# badge.net
KiCad netlist of a schematic drawn in EAGLE
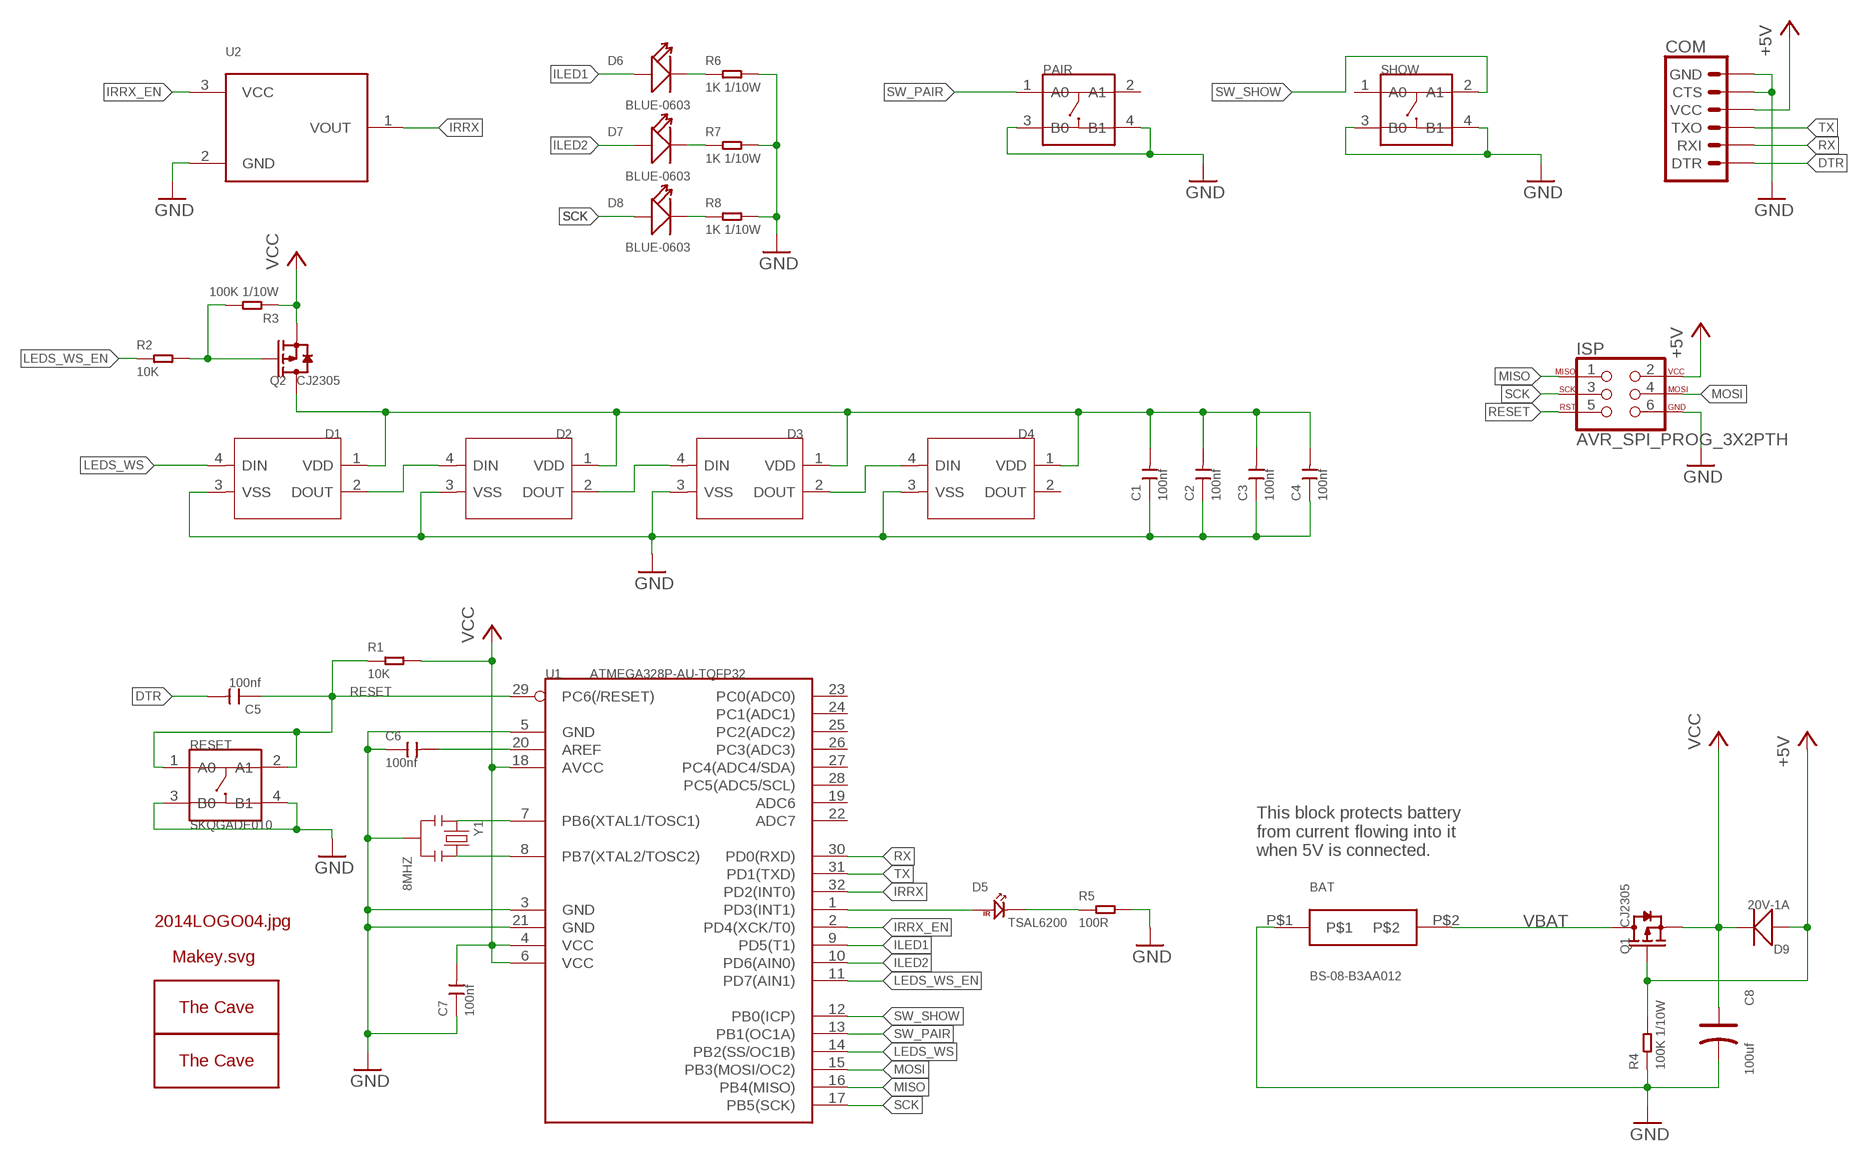
[diagram p0: schematic, sheet 1]

(export (version "E")
  (design (tool "Eeschema 10.0.6"))
  (components
    (comp (ref "BAT")
      (value "BS-08-B3AA012")
      (footprint "eagle-import:B3-08-B3AA012")
      (libsource (lib "eagle-import") (part "BS-08-B3AA012"))
    )
    (comp (ref "C1")
      (value "100nf")
      (footprint "eagle-import:C0603")
      (fields (field (name "MPN") "CC0603KRX7R9BB104"))
      (libsource (lib "eagle-import") (part "CERAMIC-100NF-50V-10%-X7R(0603)"))
    )
    (comp (ref "C2")
      (value "100nf")
      (footprint "eagle-import:C0603")
      (fields (field (name "MPN") "CC0603KRX7R9BB104"))
      (libsource (lib "eagle-import") (part "CERAMIC-100NF-50V-10%-X7R(0603)"))
    )
    (comp (ref "C3")
      (value "100nf")
      (footprint "eagle-import:C0603")
      (fields (field (name "MPN") "CC0603KRX7R9BB104"))
      (libsource (lib "eagle-import") (part "CERAMIC-100NF-50V-10%-X7R(0603)"))
    )
    (comp (ref "C4")
      (value "100nf")
      (footprint "eagle-import:C0603")
      (fields (field (name "MPN") "CC0603KRX7R9BB104"))
      (libsource (lib "eagle-import") (part "CERAMIC-100NF-50V-10%-X7R(0603)"))
    )
    (comp (ref "C5")
      (value "100nf")
      (footprint "eagle-import:C0603")
      (fields (field (name "MPN") "CC0603KRX7R9BB104"))
      (libsource (lib "eagle-import") (part "CERAMIC-100NF-50V-10%-X7R(0603)"))
    )
    (comp (ref "C6")
      (value "100nf")
      (footprint "eagle-import:C0603")
      (fields (field (name "MPN") "CC0603KRX7R9BB104"))
      (libsource (lib "eagle-import") (part "CERAMIC-100NF-50V-10%-X7R(0603)"))
    )
    (comp (ref "C7")
      (value "100nf")
      (footprint "eagle-import:C0603")
      (fields (field (name "MPN") "CC0603KRX7R9BB104"))
      (libsource (lib "eagle-import") (part "CERAMIC-100NF-50V-10%-X7R(0603)"))
    )
    (comp (ref "C8")
      (value "100uf")
      (footprint "eagle-import:AVX-B")
      (fields (field (name "MPN") "TAJB107M010#NJ"))
      (libsource (lib "eagle-import") (part "TANTALUM-SMD-100UF-10V(AVX-B)"))
    )
    (comp (ref "COM")
      (value "6_PIN_SERIAL_TARGETSILK")
      (footprint "eagle-import:6_PIN_SERIAL_TARGET_SIDE_W_SILK")
      (libsource (lib "eagle-import") (part "6_PIN_SERIAL_TARGETSILK"))
    )
    (comp (ref "D1")
      (value "SMD-RGB-LED-4P'WS2812B'")
      (footprint "eagle-import:LED4-SMD-5050")
      (libsource (lib "eagle-import") (part "SMD-RGB-LED-4P'WS2812B'"))
    )
    (comp (ref "D2")
      (value "SMD-RGB-LED-4P'WS2812B'")
      (footprint "eagle-import:LED4-SMD-5050")
      (libsource (lib "eagle-import") (part "SMD-RGB-LED-4P'WS2812B'"))
    )
    (comp (ref "D3")
      (value "SMD-RGB-LED-4P'WS2812B'")
      (footprint "eagle-import:LED4-SMD-5050")
      (libsource (lib "eagle-import") (part "SMD-RGB-LED-4P'WS2812B'"))
    )
    (comp (ref "D4")
      (value "SMD-RGB-LED-4P'WS2812B'")
      (footprint "eagle-import:LED4-SMD-5050")
      (libsource (lib "eagle-import") (part "SMD-RGB-LED-4P'WS2812B'"))
    )
    (comp (ref "D5")
      (value "TSAL6200")
      (footprint "eagle-import:TSAL6200")
      (libsource (lib "eagle-import") (part "TSAL6200"))
    )
    (comp (ref "D6")
      (value "BLUE-0603")
      (footprint "eagle-import:LED-0603")
      (fields (field (name "MPN") "19-217-BHC-ZL1M2RY-3T"))
      (libsource (lib "eagle-import") (part "SMD-LED-CLEAR-BLUE(0603)"))
    )
    (comp (ref "D7")
      (value "BLUE-0603")
      (footprint "eagle-import:LED-0603")
      (fields (field (name "MPN") "19-217-BHC-ZL1M2RY-3T"))
      (libsource (lib "eagle-import") (part "SMD-LED-CLEAR-BLUE(0603)"))
    )
    (comp (ref "D8")
      (value "BLUE-0603")
      (footprint "eagle-import:LED-0603")
      (fields (field (name "MPN") "19-217-BHC-ZL1M2RY-3T"))
      (libsource (lib "eagle-import") (part "SMD-LED-CLEAR-BLUE(0603)"))
    )
    (comp (ref "D9")
      (value "20V-1A")
      (footprint "eagle-import:SOD-123")
      (fields (field (name "MPN") "B5819W"))
      (libsource (lib "eagle-import") (part "SMD-DIODE-SCHOTTKY-20V-1A(SOD-123)"))
    )
    (comp (ref "ISP")
      (value "AVR_SPI_PROG_3X2PTH")
      (footprint "eagle-import:2X3")
      (libsource (lib "eagle-import") (part "AVR_SPI_PROG_3X2PTH"))
    )
    (comp (ref "PAIR")
      (value "SMD-BUTTON(4P-5.2X5.2X1.5MM-SKQGADE010)-SKQGADE010")
      (footprint "eagle-import:SW4-SMD-5.2X5.2X1.5MM")
      (fields (field (name "MPN") "SKQGADE010"))
      (libsource (lib "eagle-import") (part "SMD-BUTTON(4P-5.2X5.2X1.5MM-SKQGADE010)-SKQGADE010"))
    )
    (comp (ref "Q1")
      (value "CJ2305")
      (footprint "eagle-import:SOT-23")
      (libsource (lib "eagle-import") (part "SMD-MOSFET-P-CH-8V-4.1A-CJ2305(SOT-23)"))
    )
    (comp (ref "Q2")
      (value "CJ2305")
      (footprint "eagle-import:SOT-23")
      (libsource (lib "eagle-import") (part "SMD-MOSFET-P-CH-8V-4.1A-CJ2305(SOT-23)"))
    )
    (comp (ref "R1")
      (value "10K")
      (footprint "eagle-import:R0603")
      (fields (field (name "MPN") "RC0603FR-0710KL"))
      (libsource (lib "eagle-import") (part "SMD-RES-10K-1%-1/10W(0603)"))
    )
    (comp (ref "R2")
      (value "10K")
      (footprint "eagle-import:R0603")
      (fields (field (name "MPN") "RC0603FR-0710KL"))
      (libsource (lib "eagle-import") (part "SMD-RES-10K-1%-1/10W(0603)"))
    )
    (comp (ref "R3")
      (value "100K 1/10W")
      (footprint "eagle-import:R0603")
      (fields (field (name "MPN") "RC0603JR-07100KL"))
      (libsource (lib "eagle-import") (part "SMD-RES-100K-5%-1/10W(0603)"))
    )
    (comp (ref "R4")
      (value "100K 1/10W")
      (footprint "eagle-import:R0603")
      (fields (field (name "MPN") "RC0603JR-07100KL"))
      (libsource (lib "eagle-import") (part "SMD-RES-100K-5%-1/10W(0603)"))
    )
    (comp (ref "R5")
      (value "100R")
      (footprint "eagle-import:R0805")
      (fields (field (name "MPN") "RC0805JR-07100RL"))
      (libsource (lib "eagle-import") (part "SMD-RES-100R-5%-1/8W(0805)"))
    )
    (comp (ref "R6")
      (value "1K 1/10W")
      (footprint "eagle-import:R0603")
      (fields (field (name "MPN") "RC0603JR-071KL"))
      (libsource (lib "eagle-import") (part "SMD-RES-1K-5%-1/10W(0603)"))
    )
    (comp (ref "R7")
      (value "1K 1/10W")
      (footprint "eagle-import:R0603")
      (fields (field (name "MPN") "RC0603JR-071KL"))
      (libsource (lib "eagle-import") (part "SMD-RES-1K-5%-1/10W(0603)"))
    )
    (comp (ref "R8")
      (value "1K 1/10W")
      (footprint "eagle-import:R0603")
      (fields (field (name "MPN") "RC0603JR-071KL"))
      (libsource (lib "eagle-import") (part "SMD-RES-1K-5%-1/10W(0603)"))
    )
    (comp (ref "RESET")
      (value "SKQGADE010")
      (footprint "eagle-import:SW4-SMD-5.2X5.2X1.5MM")
      (libsource (lib "eagle-import") (part "SMD-BUTTON(4P-5.2X5.2X1.5MM-SKQGADE010)-SKQGADE010"))
    )
    (comp (ref "SHOW")
      (value "SMD-BUTTON(4P-5.2X5.2X1.5MM-SKQGADE010)-SKQGADE010")
      (footprint "eagle-import:SW4-SMD-5.2X5.2X1.5MM")
      (fields (field (name "MPN") "SKQGADE010"))
      (libsource (lib "eagle-import") (part "SMD-BUTTON(4P-5.2X5.2X1.5MM-SKQGADE010)-SKQGADE010"))
    )
    (comp (ref "U$1")
      (value "2014LOGO04#JPG")
      (footprint "eagle-import:2014LOGO04#JPG")
      (libsource (lib "eagle-import") (part "2014LOGO04#JPG"))
    )
    (comp (ref "U$2")
      (value "MAKEY#SVG")
      (footprint "eagle-import:MAKEY#SVG")
      (libsource (lib "eagle-import") (part "MAKEY#SVG"))
    )
    (comp (ref "U$3")
      (value "THECAVE_LOGO_NEW_TOP_SMALL")
      (footprint "eagle-import:NEW_LOGO_SMALL_TOP")
      (libsource (lib "eagle-import") (part "THECAVE_LOGO_NEW_TOP_SMALL"))
    )
    (comp (ref "U$4")
      (value "THECAVE_LOGO_NEW_COPPER_SMALL")
      (footprint "eagle-import:NEW_LOGO_SMALL_COPPER")
      (libsource (lib "eagle-import") (part "THECAVE_LOGO_NEW_COPPER_SMALL"))
    )
    (comp (ref "U1")
      (value "ATMEGA328P-AU-TQFP32")
      (footprint "eagle-import:TQFP32-0.8-7X7MM")
      (fields (field (name "MPN") "ATMEGA328P-AU"))
      (libsource (lib "eagle-import") (part "MCU-ATMEGA328P-AU(TQFP32)"))
    )
    (comp (ref "U2")
      (value "TSOP382")
      (footprint "eagle-import:TSOP382")
      (libsource (lib "eagle-import") (part "TSOP382"))
    )
    (comp (ref "Y1")
      (value "8MHZ")
      (footprint "eagle-import:X3-SMD-3.6X1.3X0.8MM")
      (libsource (lib "eagle-import") (part "SMD-CRYSTAL-8MHZ--0.3%-150R(3P-3.6X1.3MM)"))
    )
  )
  (nets
    (net (code "1") (name "+5V") (class "Default")
      (node (ref "COM") (pin "P$4") (pinfunction "VCC_P$4") (pintype "passive"))
      (node (ref "D9") (pin "+") (pinfunction "+_+") (pintype "passive"))
      (node (ref "ISP") (pin "2") (pinfunction "2_2") (pintype "passive"))
      (node (ref "Q1") (pin "1") (pinfunction "G_1") (pintype "passive"))
      (node (ref "R4") (pin "2") (pinfunction "2_2") (pintype "passive"))
    )
    (net (code "2") (name "/VBAT") (class "Default")
      (node (ref "BAT") (pin "P$2") (pinfunction "P$2_P$2") (pintype "bidirectional"))
      (node (ref "Q1") (pin "3") (pinfunction "D_3") (pintype "passive"))
    )
    (net (code "3") (name "DTR") (class "Default")
      (node (ref "C5") (pin "2") (pinfunction "2_2") (pintype "passive"))
      (node (ref "COM") (pin "P$1") (pinfunction "DTR_P$1") (pintype "passive"))
    )
    (net (code "4") (name "GND") (class "Default")
      (node (ref "BAT") (pin "P$1") (pinfunction "P$1_P$1") (pintype "bidirectional"))
      (node (ref "C1") (pin "1") (pinfunction "1_1") (pintype "passive"))
      (node (ref "C2") (pin "1") (pinfunction "1_1") (pintype "passive"))
      (node (ref "C3") (pin "1") (pinfunction "1_1") (pintype "passive"))
      (node (ref "C4") (pin "1") (pinfunction "1_1") (pintype "passive"))
      (node (ref "C6") (pin "1") (pinfunction "1_1") (pintype "passive"))
      (node (ref "C7") (pin "1") (pinfunction "1_1") (pintype "passive"))
      (node (ref "C8") (pin "-") (pinfunction "-_-") (pintype "passive"))
      (node (ref "COM") (pin "P$5") (pinfunction "CTS_P$5") (pintype "passive"))
      (node (ref "COM") (pin "P$6") (pinfunction "GND_P$6") (pintype "passive"))
      (node (ref "D1") (pin "3") (pinfunction "VSS_3") (pintype "bidirectional"))
      (node (ref "D2") (pin "3") (pinfunction "VSS_3") (pintype "bidirectional"))
      (node (ref "D3") (pin "3") (pinfunction "VSS_3") (pintype "bidirectional"))
      (node (ref "D4") (pin "3") (pinfunction "VSS_3") (pintype "bidirectional"))
      (node (ref "ISP") (pin "6") (pinfunction "6_6") (pintype "passive"))
      (node (ref "PAIR") (pin "3") (pinfunction "B0_3") (pintype "bidirectional"))
      (node (ref "PAIR") (pin "4") (pinfunction "B1_4") (pintype "bidirectional"))
      (node (ref "R4") (pin "1") (pinfunction "1_1") (pintype "passive"))
      (node (ref "R5") (pin "2") (pinfunction "2_2") (pintype "passive"))
      (node (ref "R6") (pin "2") (pinfunction "2_2") (pintype "passive"))
      (node (ref "R7") (pin "2") (pinfunction "2_2") (pintype "passive"))
      (node (ref "R8") (pin "2") (pinfunction "2_2") (pintype "passive"))
      (node (ref "RESET") (pin "3") (pinfunction "B0_3") (pintype "bidirectional"))
      (node (ref "RESET") (pin "4") (pinfunction "B1_4") (pintype "bidirectional"))
      (node (ref "SHOW") (pin "3") (pinfunction "B0_3") (pintype "bidirectional"))
      (node (ref "SHOW") (pin "4") (pinfunction "B1_4") (pintype "bidirectional"))
      (node (ref "U1") (pin "21") (pinfunction "GND_21") (pintype "bidirectional"))
      (node (ref "U1") (pin "3") (pinfunction "GND_3") (pintype "bidirectional"))
      (node (ref "U1") (pin "5") (pinfunction "GND_5") (pintype "bidirectional"))
      (node (ref "U2") (pin "2") (pinfunction "GND_2") (pintype "bidirectional"))
      (node (ref "Y1") (pin "2") (pinfunction "2_2") (pintype "passive"))
    )
    (net (code "5") (name "ILED1") (class "Default")
      (node (ref "D6") (pin "+") (pinfunction "+_+") (pintype "passive"))
      (node (ref "U1") (pin "9") (pinfunction "PD5(T1)_9") (pintype "bidirectional"))
    )
    (net (code "6") (name "ILED2") (class "Default")
      (node (ref "D7") (pin "+") (pinfunction "+_+") (pintype "passive"))
      (node (ref "U1") (pin "10") (pinfunction "PD6(AIN0)_10") (pintype "bidirectional"))
    )
    (net (code "7") (name "IRRX") (class "Default")
      (node (ref "U1") (pin "32") (pinfunction "PD2(INT0)_32") (pintype "bidirectional"))
      (node (ref "U2") (pin "1") (pinfunction "VOUT_1") (pintype "bidirectional"))
    )
    (net (code "8") (name "IRRX_EN") (class "Default")
      (node (ref "U1") (pin "2") (pinfunction "PD4(XCK/T0)_2") (pintype "bidirectional"))
      (node (ref "U2") (pin "3") (pinfunction "VCC_3") (pintype "bidirectional"))
    )
    (net (code "9") (name "LEDS_WS") (class "Default")
      (node (ref "D1") (pin "4") (pinfunction "DIN_4") (pintype "bidirectional"))
      (node (ref "U1") (pin "14") (pinfunction "PB2(SS/OC1B)_14") (pintype "bidirectional"))
    )
    (net (code "10") (name "LEDS_WS_EN") (class "Default")
      (node (ref "R2") (pin "1") (pinfunction "1_1") (pintype "passive"))
      (node (ref "U1") (pin "11") (pinfunction "PD7(AIN1)_11") (pintype "bidirectional"))
    )
    (net (code "11") (name "MISO") (class "Default")
      (node (ref "ISP") (pin "1") (pinfunction "1_1") (pintype "passive"))
      (node (ref "U1") (pin "16") (pinfunction "PB4(MISO)_16") (pintype "bidirectional"))
    )
    (net (code "12") (name "MOSI") (class "Default")
      (node (ref "ISP") (pin "4") (pinfunction "4_4") (pintype "passive"))
      (node (ref "U1") (pin "15") (pinfunction "PB3(MOSI/OC2)_15") (pintype "bidirectional"))
    )
    (net (code "13") (name "Net-(D1-DOUT)") (class "Default")
      (node (ref "D1") (pin "2") (pinfunction "DOUT_2") (pintype "bidirectional"))
      (node (ref "D2") (pin "4") (pinfunction "DIN_4") (pintype "bidirectional"))
    )
    (net (code "14") (name "Net-(D1-VDD)") (class "Default")
      (node (ref "C1") (pin "2") (pinfunction "2_2") (pintype "passive"))
      (node (ref "C2") (pin "2") (pinfunction "2_2") (pintype "passive"))
      (node (ref "C3") (pin "2") (pinfunction "2_2") (pintype "passive"))
      (node (ref "C4") (pin "2") (pinfunction "2_2") (pintype "passive"))
      (node (ref "D1") (pin "1") (pinfunction "VDD_1") (pintype "bidirectional"))
      (node (ref "D2") (pin "1") (pinfunction "VDD_1") (pintype "bidirectional"))
      (node (ref "D3") (pin "1") (pinfunction "VDD_1") (pintype "bidirectional"))
      (node (ref "D4") (pin "1") (pinfunction "VDD_1") (pintype "bidirectional"))
      (node (ref "Q2") (pin "3") (pinfunction "D_3") (pintype "passive"))
    )
    (net (code "15") (name "Net-(D2-DOUT)") (class "Default")
      (node (ref "D2") (pin "2") (pinfunction "DOUT_2") (pintype "bidirectional"))
      (node (ref "D3") (pin "4") (pinfunction "DIN_4") (pintype "bidirectional"))
    )
    (net (code "16") (name "Net-(D3-DOUT)") (class "Default")
      (node (ref "D3") (pin "2") (pinfunction "DOUT_2") (pintype "bidirectional"))
      (node (ref "D4") (pin "4") (pinfunction "DIN_4") (pintype "bidirectional"))
    )
    (net (code "17") (name "Net-(D5-PadN)") (class "Default")
      (node (ref "D5") (pin "N") (pinfunction "N_N") (pintype "bidirectional"))
      (node (ref "R5") (pin "1") (pinfunction "1_1") (pintype "passive"))
    )
    (net (code "18") (name "Net-(D6-Pad-)") (class "Default")
      (node (ref "D6") (pin "-") (pinfunction "-_-") (pintype "passive"))
      (node (ref "R6") (pin "1") (pinfunction "1_1") (pintype "passive"))
    )
    (net (code "19") (name "Net-(D7-Pad-)") (class "Default")
      (node (ref "D7") (pin "-") (pinfunction "-_-") (pintype "passive"))
      (node (ref "R7") (pin "1") (pinfunction "1_1") (pintype "passive"))
    )
    (net (code "20") (name "Net-(D8-Pad-)") (class "Default")
      (node (ref "D8") (pin "-") (pinfunction "-_-") (pintype "passive"))
      (node (ref "R8") (pin "1") (pinfunction "1_1") (pintype "passive"))
    )
    (net (code "21") (name "Net-(Q2-G)") (class "Default")
      (node (ref "Q2") (pin "1") (pinfunction "G_1") (pintype "passive"))
      (node (ref "R2") (pin "2") (pinfunction "2_2") (pintype "passive"))
      (node (ref "R3") (pin "2") (pinfunction "2_2") (pintype "passive"))
    )
    (net (code "22") (name "Net-(U1-AREF)") (class "Default")
      (node (ref "C6") (pin "2") (pinfunction "2_2") (pintype "passive"))
      (node (ref "U1") (pin "20") (pinfunction "AREF_20") (pintype "bidirectional"))
    )
    (net (code "23") (name "Net-(U1-PB6(XTAL1{slash}TOSC1))") (class "Default")
      (node (ref "U1") (pin "7") (pinfunction "PB6(XTAL1/TOSC1)_7") (pintype "bidirectional"))
      (node (ref "Y1") (pin "1") (pinfunction "1_1") (pintype "passive"))
    )
    (net (code "24") (name "Net-(U1-PB7(XTAL2{slash}TOSC2))") (class "Default")
      (node (ref "U1") (pin "8") (pinfunction "PB7(XTAL2/TOSC2)_8") (pintype "bidirectional"))
      (node (ref "Y1") (pin "3") (pinfunction "3_3") (pintype "passive"))
    )
    (net (code "25") (name "Net-(U1-PD3(INT1))") (class "Default")
      (node (ref "D5") (pin "P") (pinfunction "P_P") (pintype "bidirectional"))
      (node (ref "U1") (pin "1") (pinfunction "PD3(INT1)_1") (pintype "bidirectional"))
    )
    (net (code "26") (name "RESET") (class "Default")
      (node (ref "C5") (pin "1") (pinfunction "1_1") (pintype "passive"))
      (node (ref "ISP") (pin "5") (pinfunction "5_5") (pintype "passive"))
      (node (ref "R1") (pin "1") (pinfunction "1_1") (pintype "passive"))
      (node (ref "RESET") (pin "1") (pinfunction "A0_1") (pintype "bidirectional"))
      (node (ref "RESET") (pin "2") (pinfunction "A1_2") (pintype "bidirectional"))
      (node (ref "U1") (pin "29") (pinfunction "PC6(/RESET)_29") (pintype "bidirectional"))
    )
    (net (code "27") (name "RX") (class "Default")
      (node (ref "COM") (pin "P$3") (pinfunction "RXI_P$3") (pintype "passive"))
      (node (ref "U1") (pin "30") (pinfunction "PD0(RXD)_30") (pintype "bidirectional"))
    )
    (net (code "28") (name "SCK") (class "Default")
      (node (ref "D8") (pin "+") (pinfunction "+_+") (pintype "passive"))
      (node (ref "ISP") (pin "3") (pinfunction "3_3") (pintype "passive"))
      (node (ref "U1") (pin "17") (pinfunction "PB5(SCK)_17") (pintype "bidirectional"))
    )
    (net (code "29") (name "SW_PAIR") (class "Default")
      (node (ref "PAIR") (pin "1") (pinfunction "A0_1") (pintype "bidirectional"))
      (node (ref "U1") (pin "13") (pinfunction "PB1(OC1A)_13") (pintype "bidirectional"))
    )
    (net (code "30") (name "SW_SHOW") (class "Default")
      (node (ref "SHOW") (pin "2") (pinfunction "A1_2") (pintype "bidirectional"))
      (node (ref "U1") (pin "12") (pinfunction "PB0(ICP)_12") (pintype "bidirectional"))
    )
    (net (code "31") (name "TX") (class "Default")
      (node (ref "COM") (pin "P$2") (pinfunction "TXO_P$2") (pintype "passive"))
      (node (ref "U1") (pin "31") (pinfunction "PD1(TXD)_31") (pintype "bidirectional"))
    )
    (net (code "32") (name "VCC") (class "Default")
      (node (ref "C7") (pin "2") (pinfunction "2_2") (pintype "passive"))
      (node (ref "C8") (pin "+") (pinfunction "+_+") (pintype "passive"))
      (node (ref "D9") (pin "-") (pinfunction "-_-") (pintype "passive"))
      (node (ref "Q1") (pin "2") (pinfunction "S_2") (pintype "passive"))
      (node (ref "Q2") (pin "2") (pinfunction "S_2") (pintype "passive"))
      (node (ref "R1") (pin "2") (pinfunction "2_2") (pintype "passive"))
      (node (ref "R3") (pin "1") (pinfunction "1_1") (pintype "passive"))
      (node (ref "U1") (pin "18") (pinfunction "AVCC_18") (pintype "bidirectional"))
      (node (ref "U1") (pin "4") (pinfunction "VCC_4") (pintype "bidirectional"))
      (node (ref "U1") (pin "6") (pinfunction "VCC_6") (pintype "bidirectional"))
    )
    (net (code "33") (name "unconnected-(D4-DOUT-Pad2)") (class "Default")
      (node (ref "D4") (pin "2") (pinfunction "DOUT_2") (pintype "bidirectional"))
    )
    (net (code "34") (name "unconnected-(PAIR-A1-Pad2)") (class "Default")
      (node (ref "PAIR") (pin "2") (pinfunction "A1_2") (pintype "bidirectional"))
    )
    (net (code "35") (name "unconnected-(SHOW-A0-Pad1)") (class "Default")
      (node (ref "SHOW") (pin "1") (pinfunction "A0_1") (pintype "bidirectional"))
    )
    (net (code "36") (name "unconnected-(U1-ADC6-Pad19)") (class "Default")
      (node (ref "U1") (pin "19") (pinfunction "ADC6_19") (pintype "bidirectional"))
    )
    (net (code "37") (name "unconnected-(U1-ADC7-Pad22)") (class "Default")
      (node (ref "U1") (pin "22") (pinfunction "ADC7_22") (pintype "bidirectional"))
    )
    (net (code "38") (name "unconnected-(U1-PC0(ADC0)-Pad23)") (class "Default")
      (node (ref "U1") (pin "23") (pinfunction "PC0(ADC0)_23") (pintype "bidirectional"))
    )
    (net (code "39") (name "unconnected-(U1-PC1(ADC1)-Pad24)") (class "Default")
      (node (ref "U1") (pin "24") (pinfunction "PC1(ADC1)_24") (pintype "bidirectional"))
    )
    (net (code "40") (name "unconnected-(U1-PC2(ADC2)-Pad25)") (class "Default")
      (node (ref "U1") (pin "25") (pinfunction "PC2(ADC2)_25") (pintype "bidirectional"))
    )
    (net (code "41") (name "unconnected-(U1-PC3(ADC3)-Pad26)") (class "Default")
      (node (ref "U1") (pin "26") (pinfunction "PC3(ADC3)_26") (pintype "bidirectional"))
    )
    (net (code "42") (name "unconnected-(U1-PC4(ADC4{slash}SDA)-Pad27)") (class "Default")
      (node (ref "U1") (pin "27") (pinfunction "PC4(ADC4/SDA)_27") (pintype "bidirectional"))
    )
    (net (code "43") (name "unconnected-(U1-PC5(ADC5{slash}SCL)-Pad28)") (class "Default")
      (node (ref "U1") (pin "28") (pinfunction "PC5(ADC5/SCL)_28") (pintype "bidirectional"))
    )
  )
)
